# PCU_Testboard.net
KiCad netlist of a schematic drawn in EAGLE
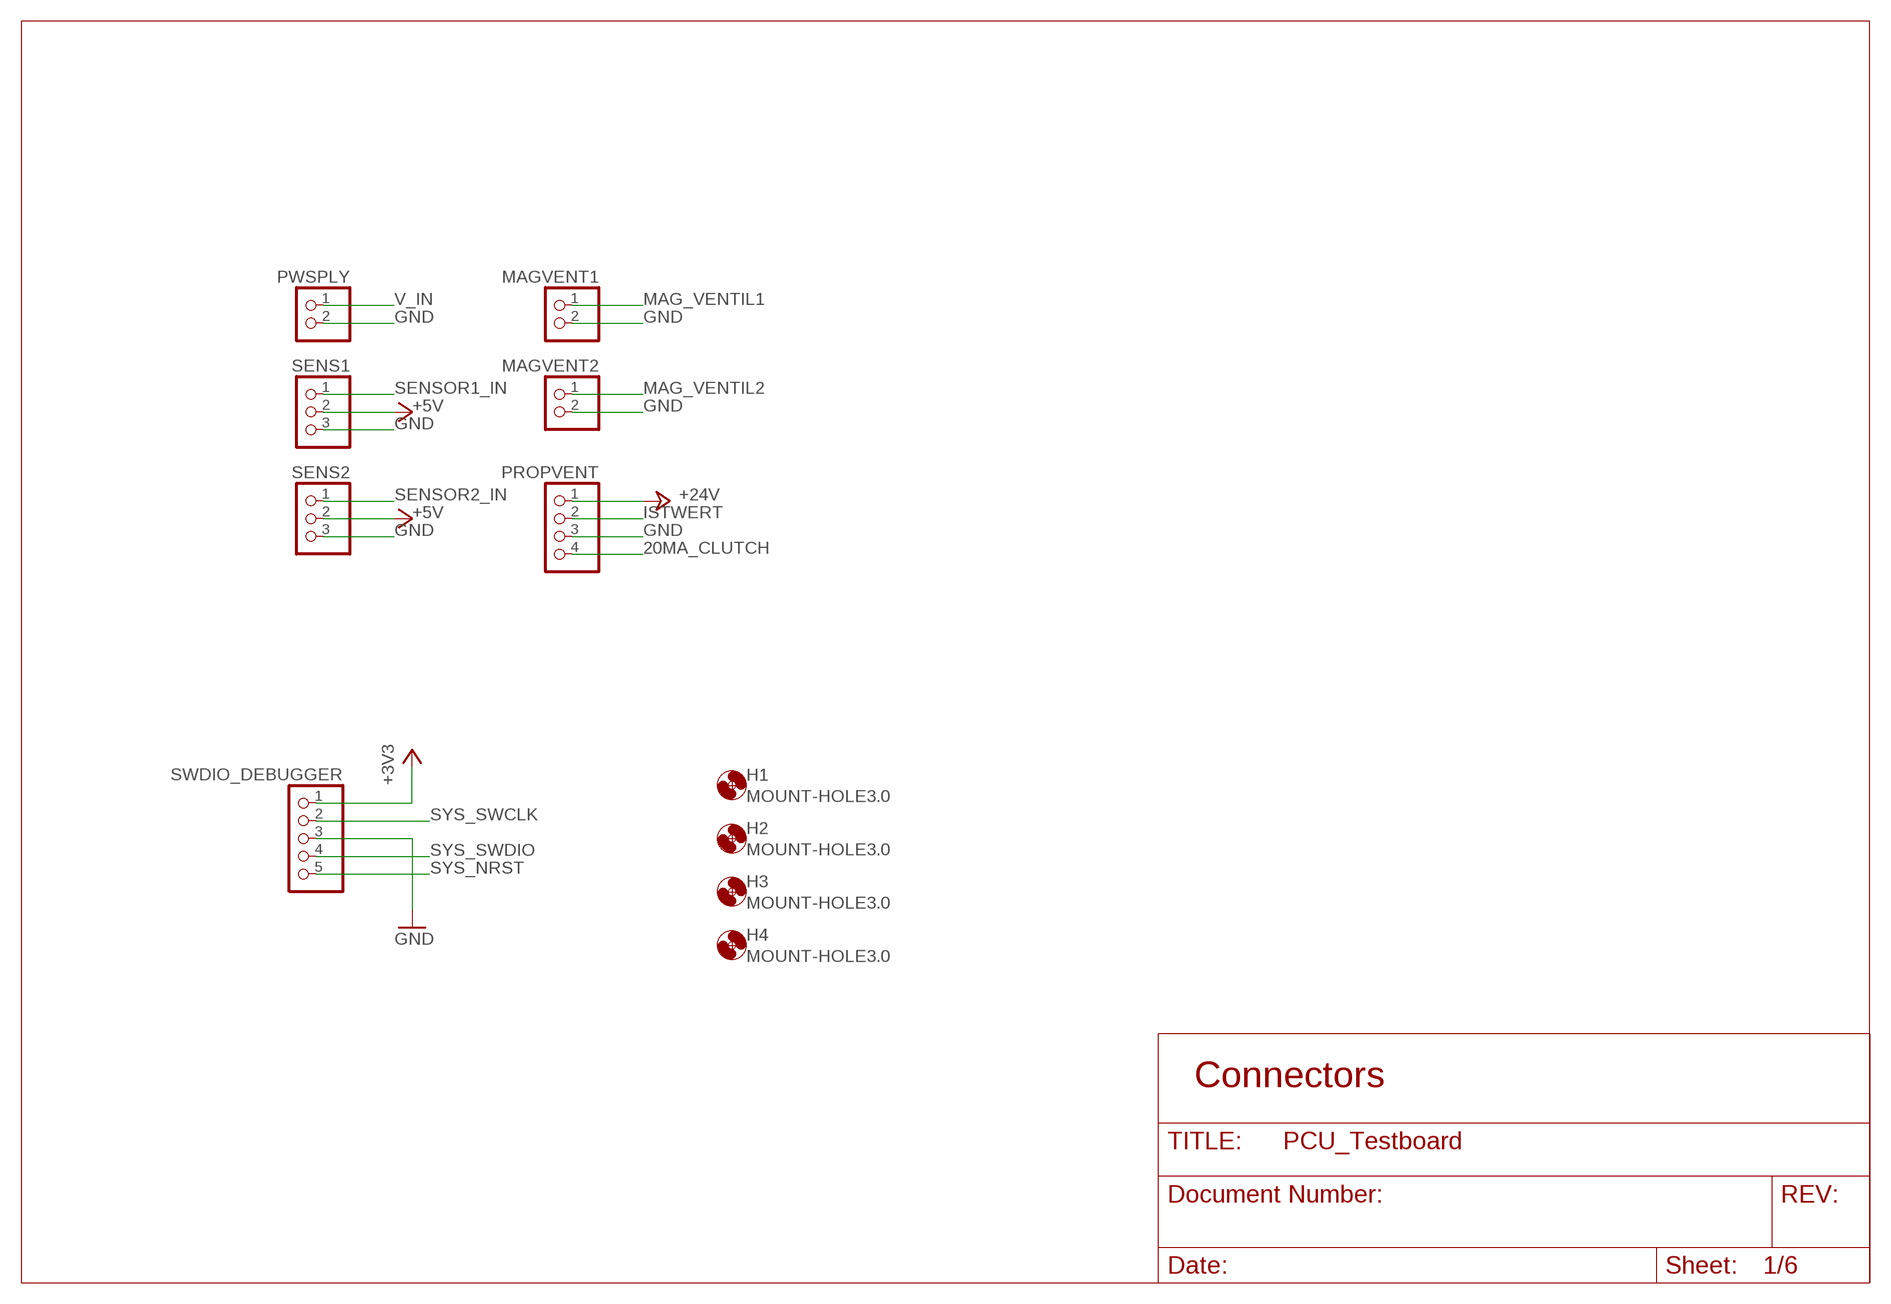
[diagram p0: schematic, sheet 1]
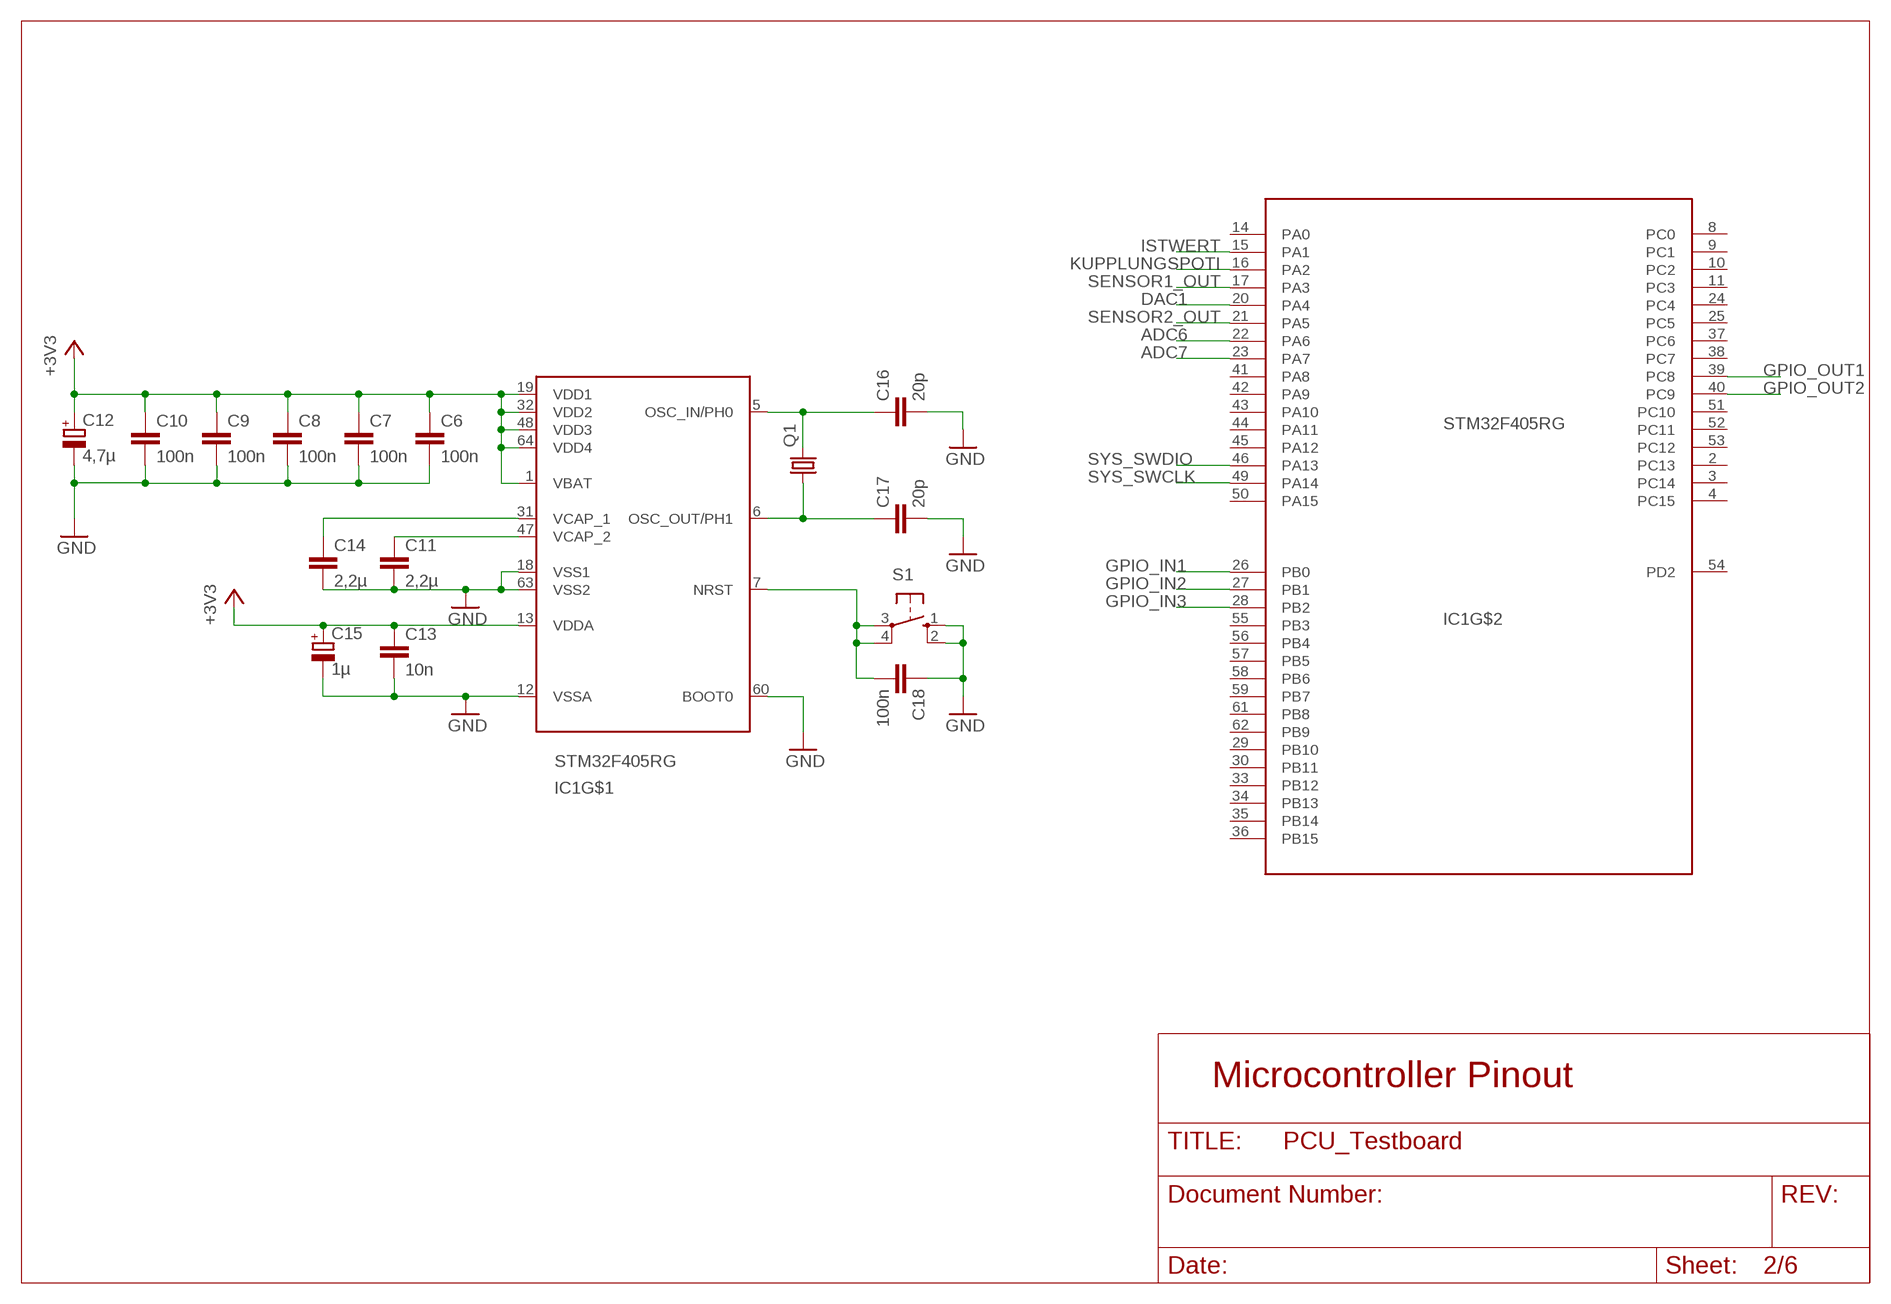
[diagram p1: schematic, sheet 2]
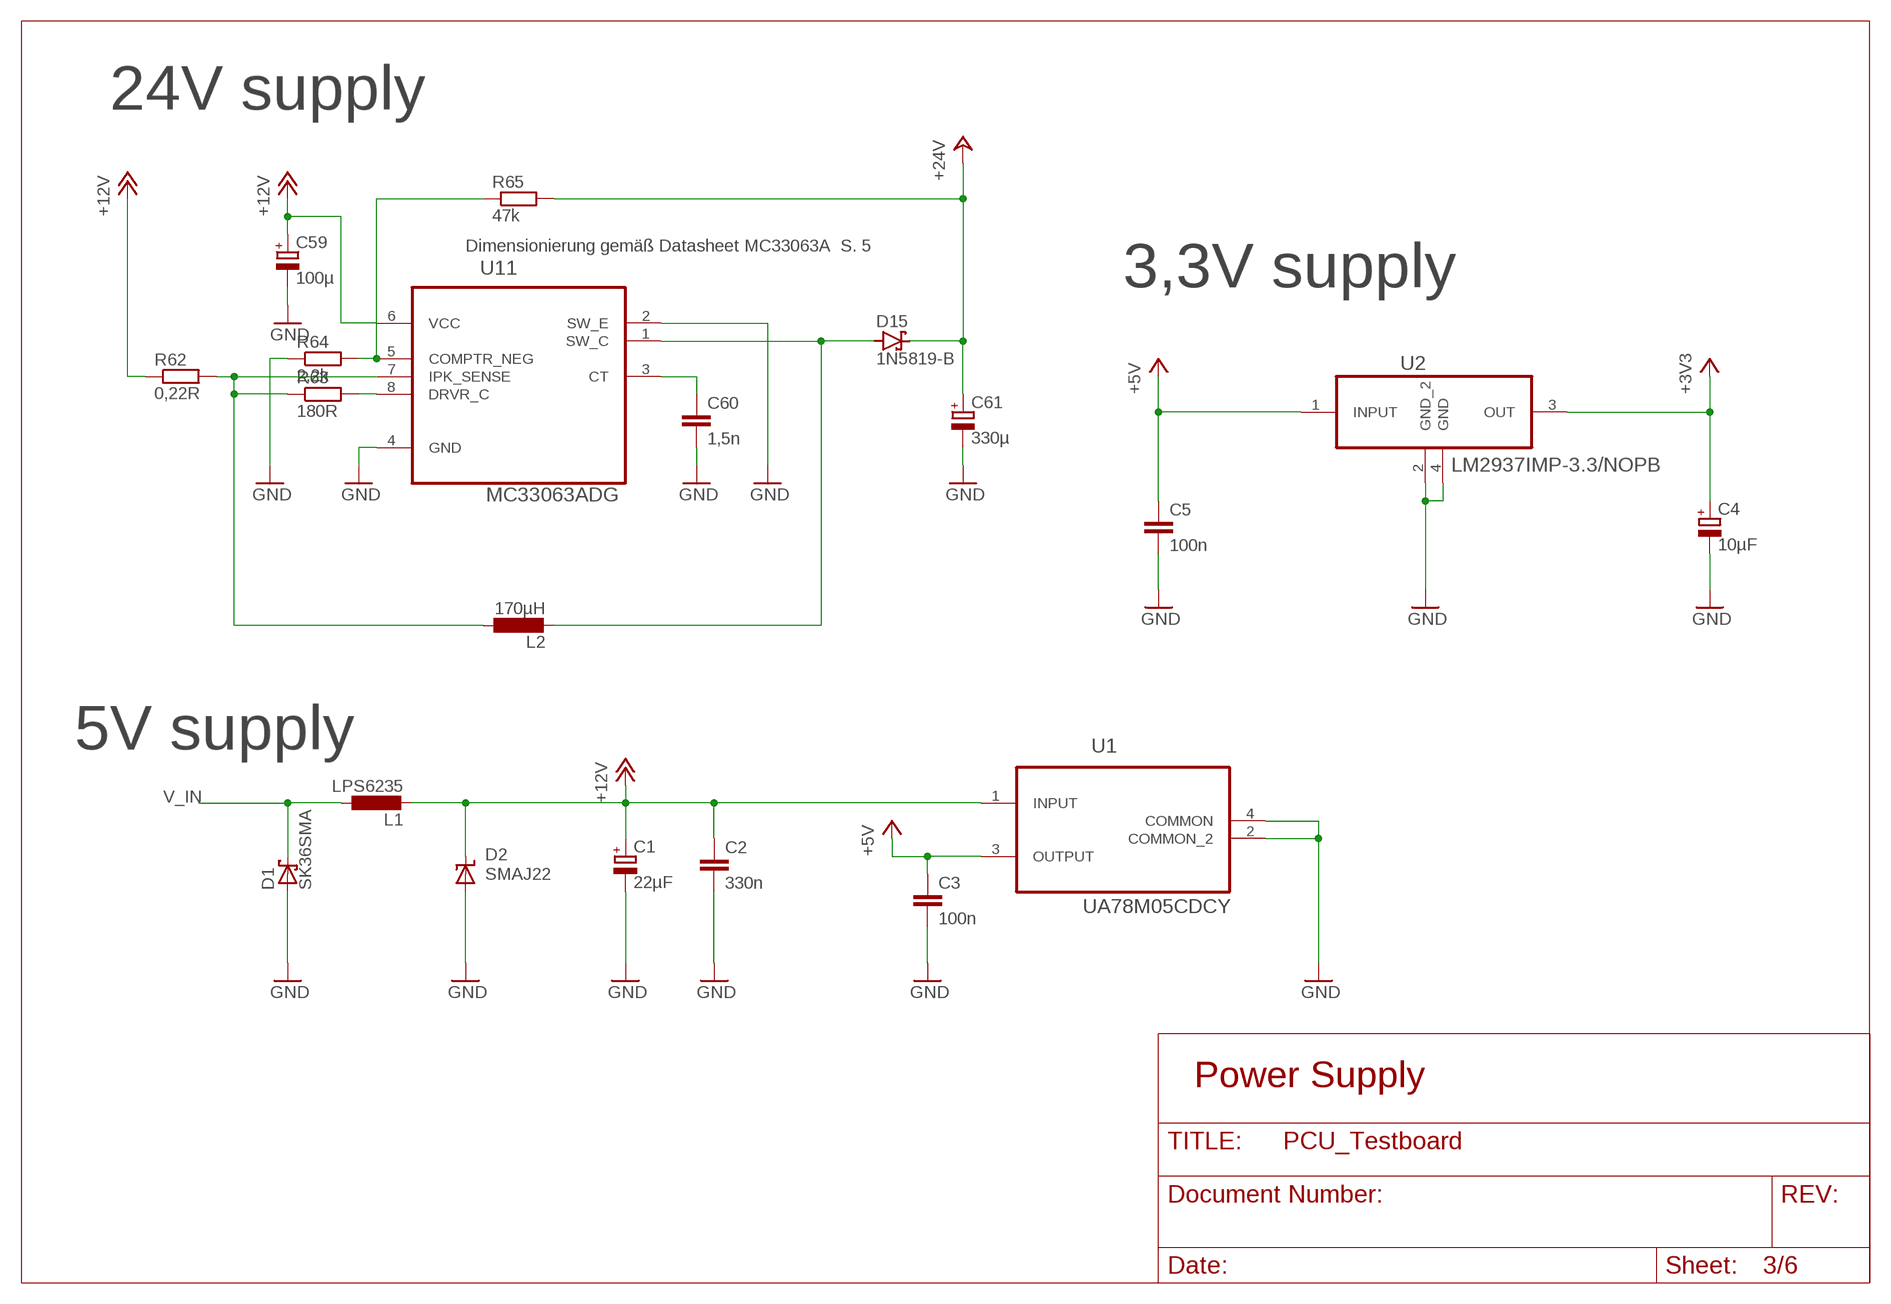
[diagram p2: schematic, sheet 3]
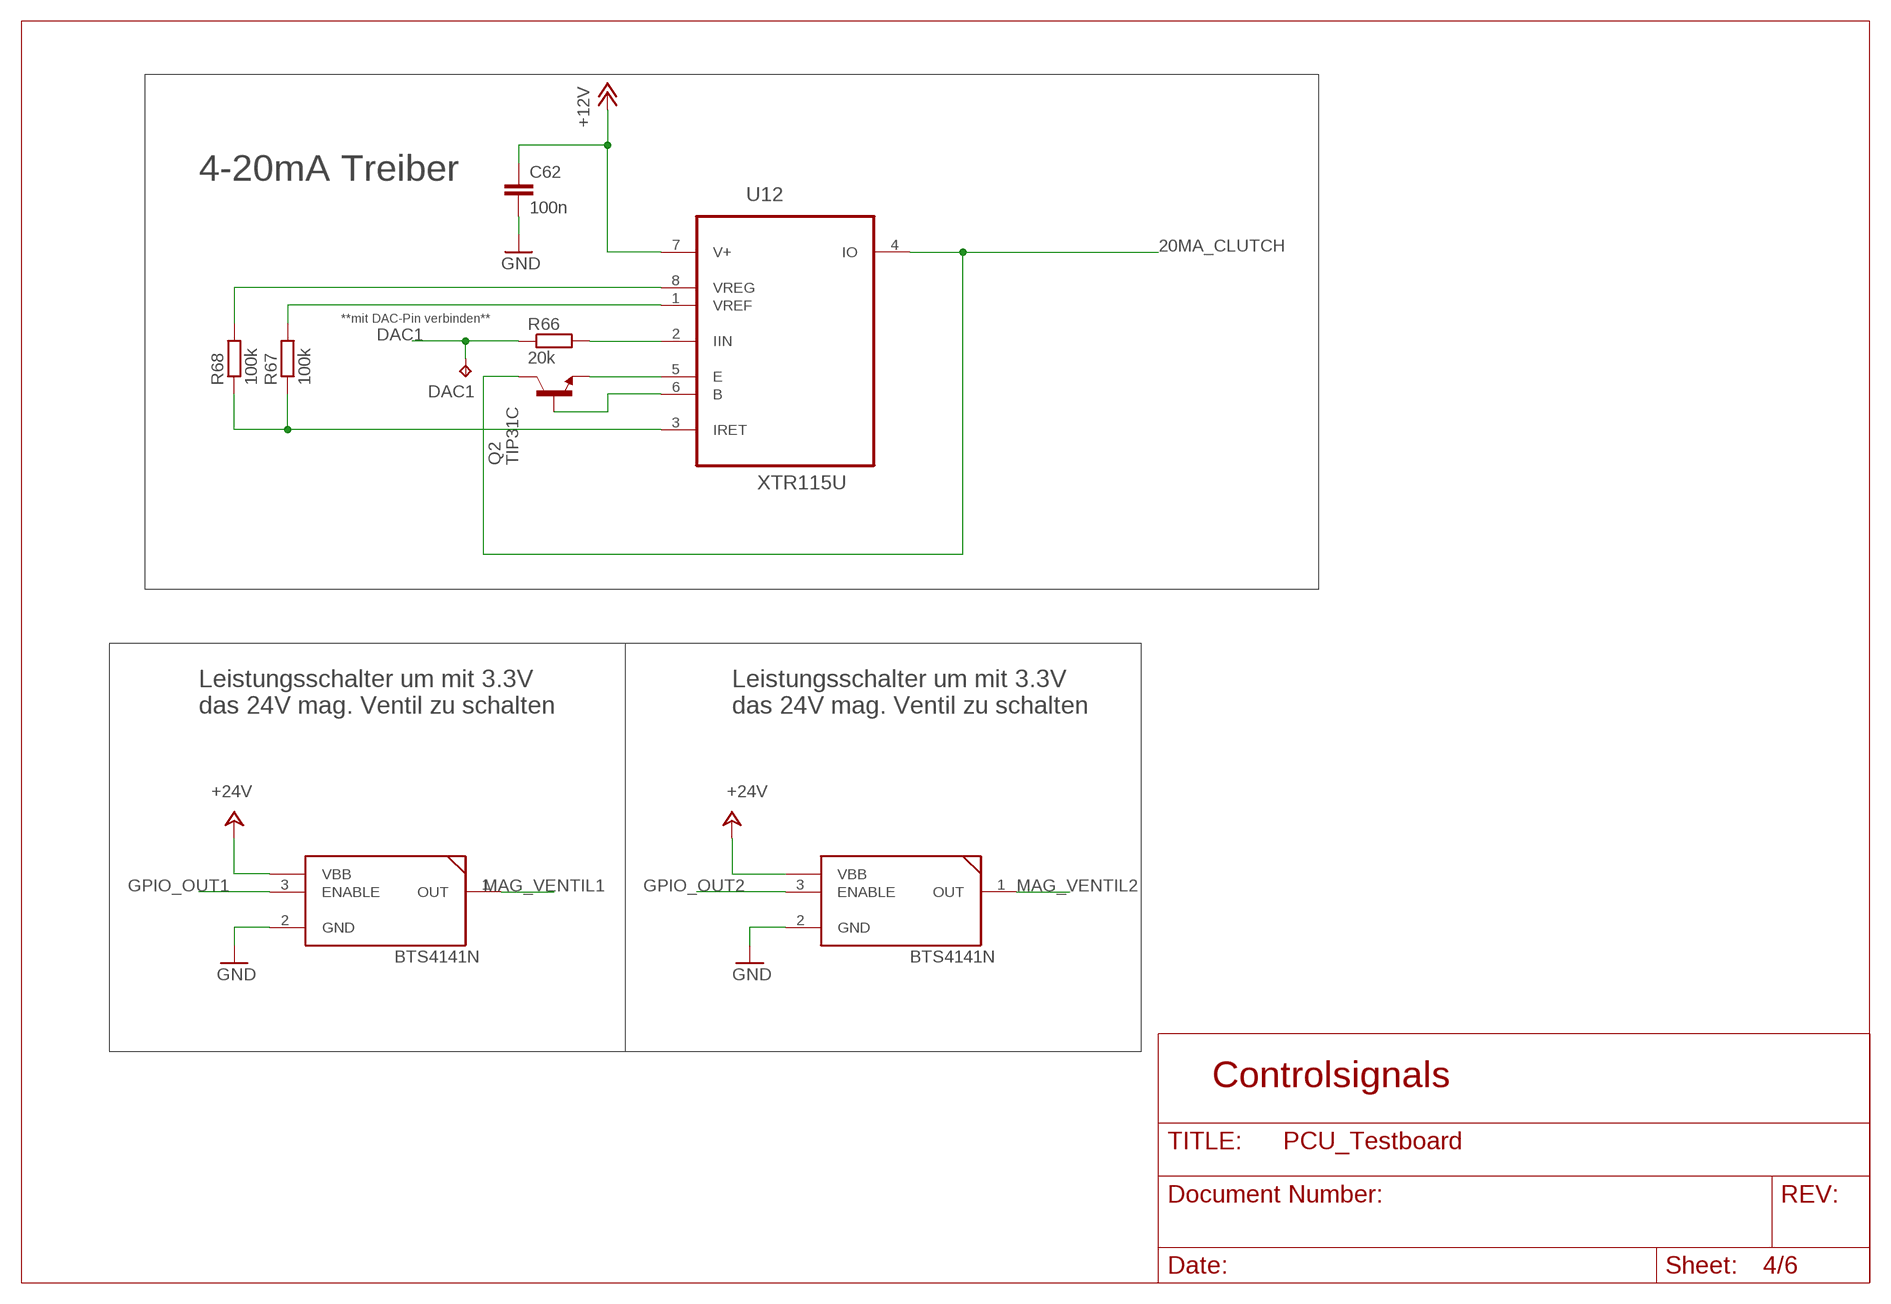
[diagram p3: schematic, sheet 4]
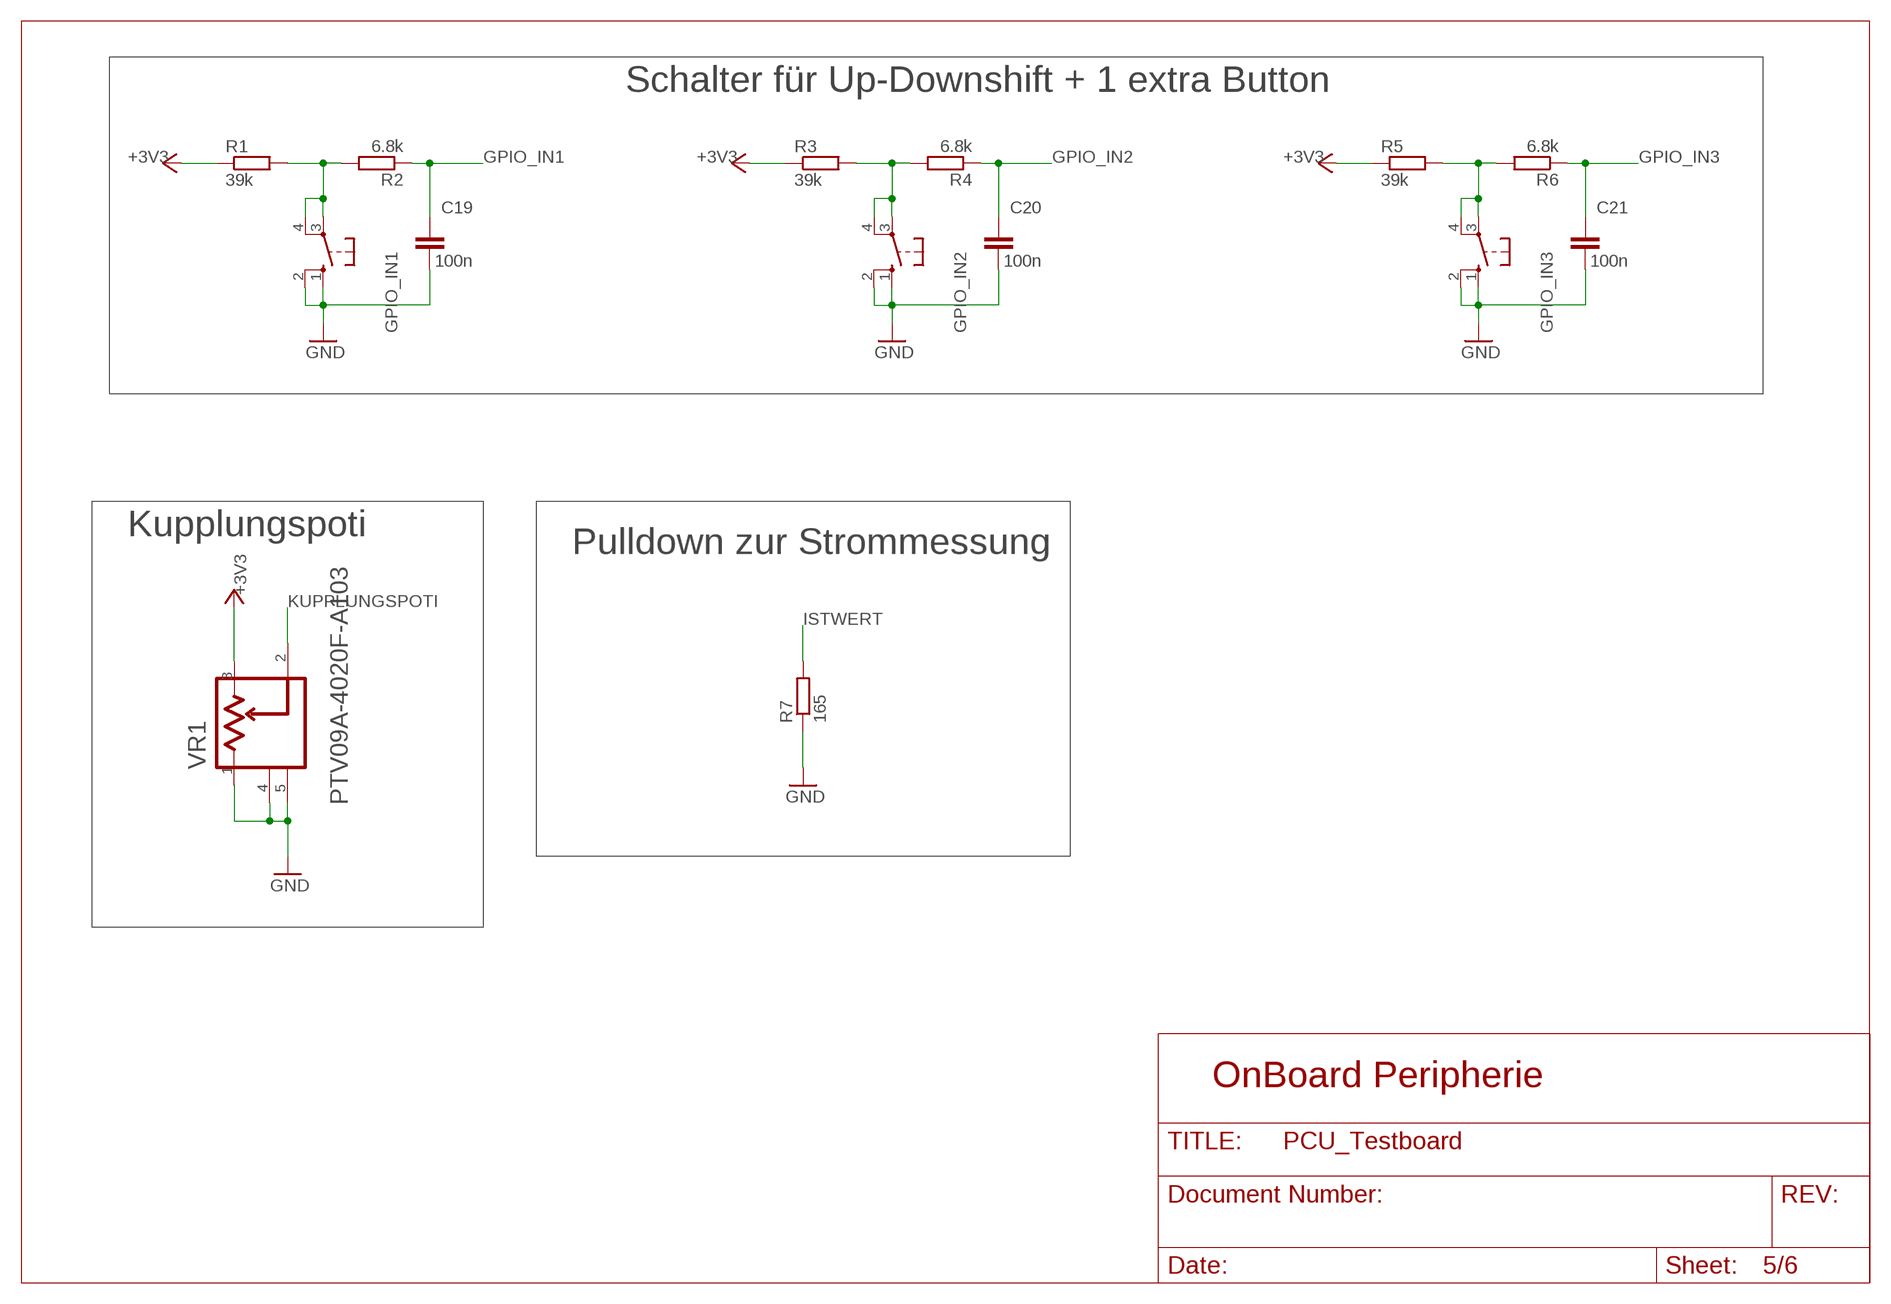
[diagram p4: schematic, sheet 5]
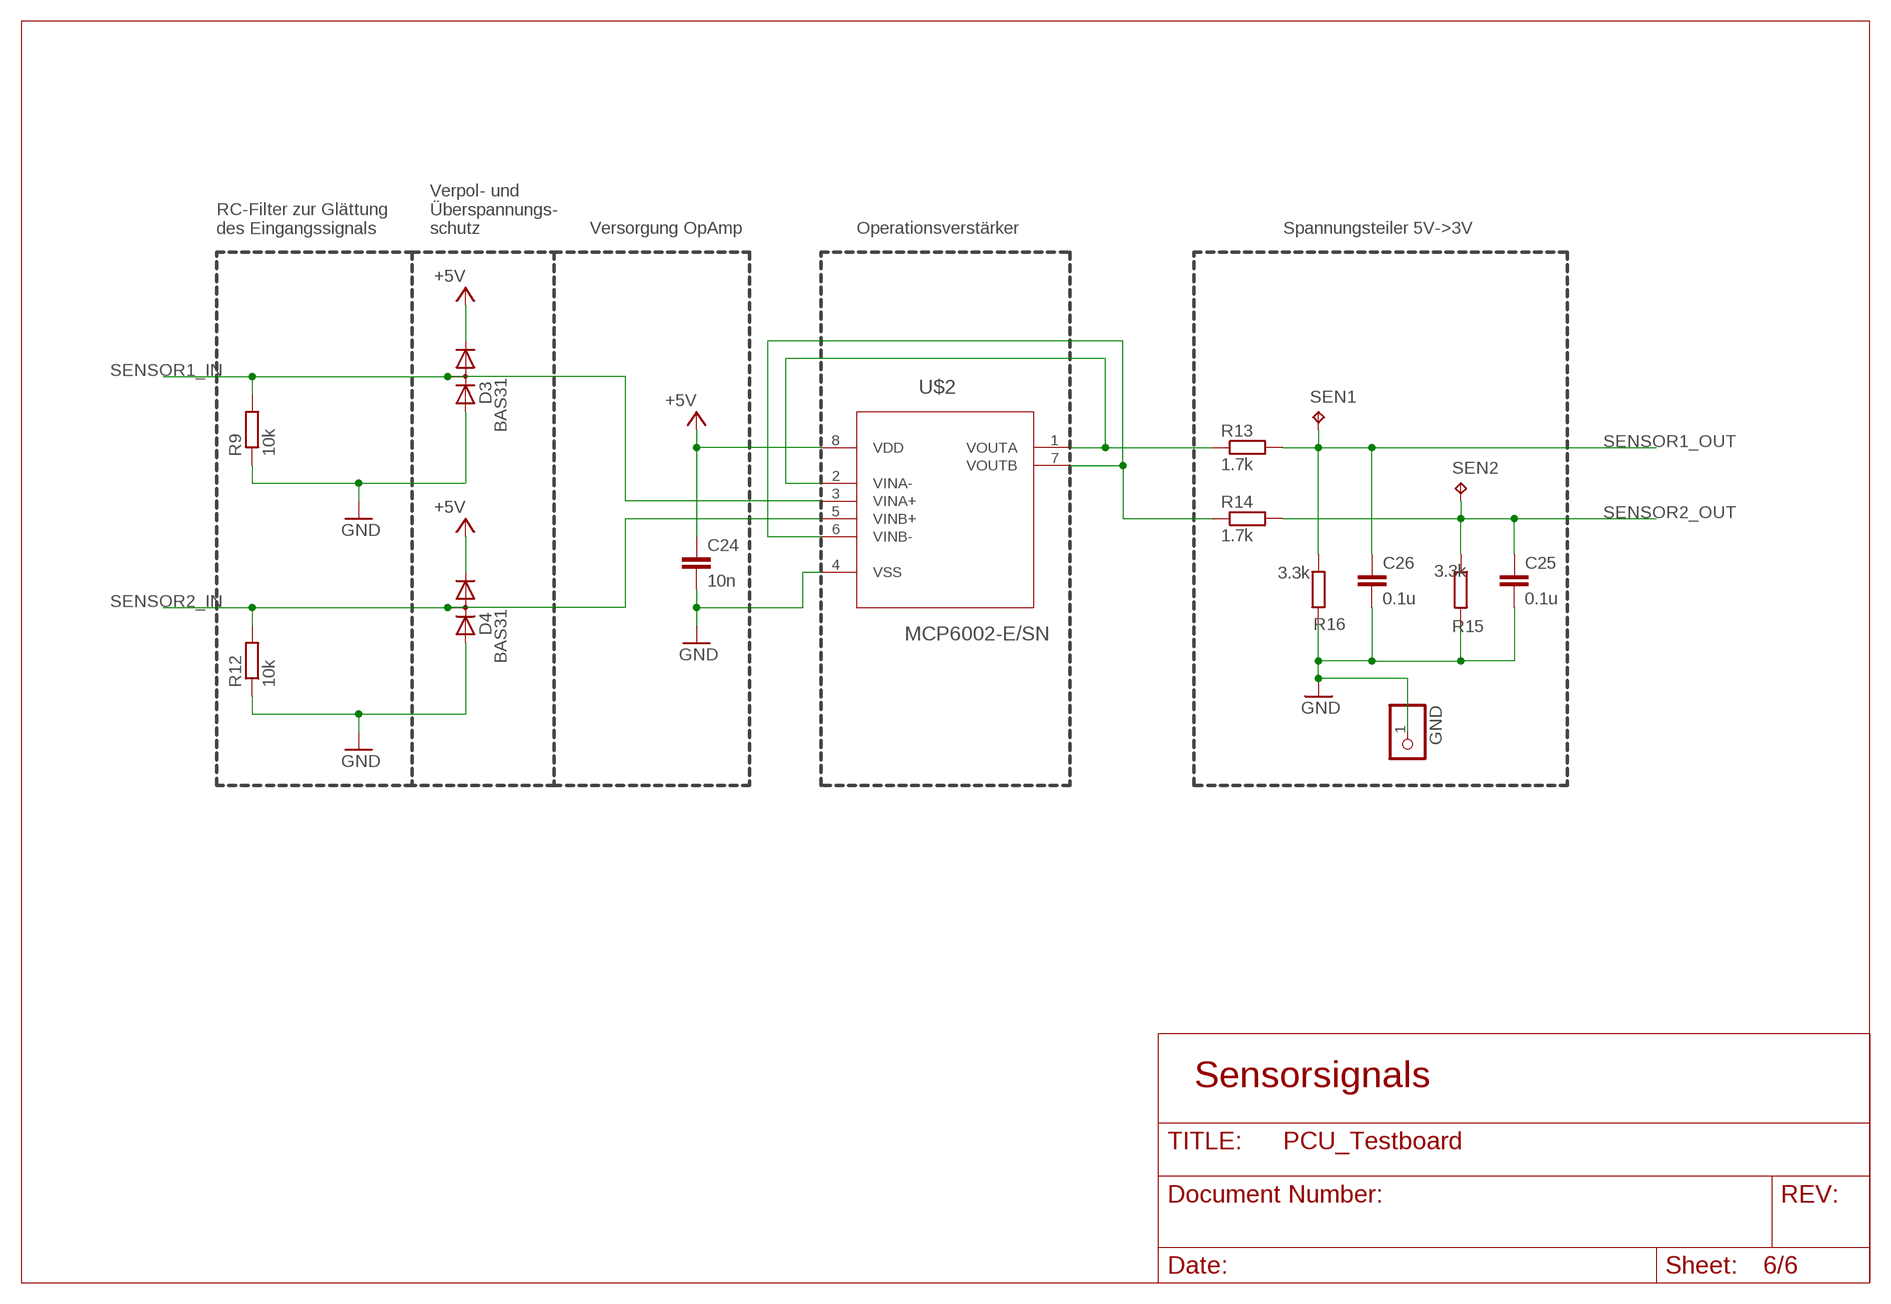
[diagram p5: schematic, sheet 6]

(export (version "E")
  (design (tool "Eeschema 10.0.6"))
  (components
    (comp (ref "C6")
      (value "100n")
      (footprint "eagle-import:C0603")
      (libsource (lib "eagle-import") (part "C-EUC0603"))
    )
    (comp (ref "C7")
      (value "100n")
      (footprint "eagle-import:C0603")
      (libsource (lib "eagle-import") (part "C-EUC0603"))
    )
    (comp (ref "C8")
      (value "100n")
      (footprint "eagle-import:C0603")
      (libsource (lib "eagle-import") (part "C-EUC0603"))
    )
    (comp (ref "C9")
      (value "100n")
      (footprint "eagle-import:C0603")
      (libsource (lib "eagle-import") (part "C-EUC0603"))
    )
    (comp (ref "C10")
      (value "100n")
      (footprint "eagle-import:C0603")
      (libsource (lib "eagle-import") (part "C-EUC0603"))
    )
    (comp (ref "C11")
      (value "2,2µ")
      (footprint "eagle-import:C0603")
      (libsource (lib "eagle-import") (part "C-EUC0603"))
    )
    (comp (ref "C12")
      (value "4,7µ")
      (footprint "eagle-import:153CLV-0505")
      (libsource (lib "eagle-import") (part "CPOL-EU153CLV-0505"))
    )
    (comp (ref "C13")
      (value "10n")
      (footprint "eagle-import:C0603")
      (libsource (lib "eagle-import") (part "C-EUC0603"))
    )
    (comp (ref "C14")
      (value "2,2µ")
      (footprint "eagle-import:C0603")
      (libsource (lib "eagle-import") (part "C-EUC0603"))
    )
    (comp (ref "C15")
      (value "1µ")
      (footprint "eagle-import:153CLV-0505")
      (libsource (lib "eagle-import") (part "CPOL-EU153CLV-0505"))
    )
    (comp (ref "C16")
      (value "20p")
      (footprint "eagle-import:C0603")
      (libsource (lib "eagle-import") (part "C-EUC0603"))
    )
    (comp (ref "C17")
      (value "20p")
      (footprint "eagle-import:C0603")
      (libsource (lib "eagle-import") (part "C-EUC0603"))
    )
    (comp (ref "C18")
      (value "100n")
      (footprint "eagle-import:C0603")
      (libsource (lib "eagle-import") (part "C-EUC0603"))
    )
    (comp (ref "IC1")
      (value "STM32F405RG")
      (footprint "eagle-import:LQFP64")
      (libsource (lib "eagle-import") (part "STM32F405RG"))
    )
    (comp (ref "Q1")
      (value "CRYSTALHC49UP")
      (footprint "eagle-import:HC49UP")
      (libsource (lib "eagle-import") (part "CRYSTALHC49UP"))
    )
    (comp (ref "S1")
      (value "10-XX")
      (footprint "eagle-import:B3F-10XX")
      (fields (field (name "MPN") "B3F-1000"))
      (libsource (lib "eagle-import") (part "10-XX"))
    )
    (comp (ref "H1")
      (value "MOUNT-HOLE3.0")
      (footprint "eagle-import:3,0")
      (libsource (lib "eagle-import") (part "MOUNT-HOLE3.0"))
    )
    (comp (ref "H2")
      (value "MOUNT-HOLE3.0")
      (footprint "eagle-import:3,0")
      (libsource (lib "eagle-import") (part "MOUNT-HOLE3.0"))
    )
    (comp (ref "H3")
      (value "MOUNT-HOLE3.0")
      (footprint "eagle-import:3,0")
      (libsource (lib "eagle-import") (part "MOUNT-HOLE3.0"))
    )
    (comp (ref "H4")
      (value "MOUNT-HOLE3.0")
      (footprint "eagle-import:3,0")
      (libsource (lib "eagle-import") (part "MOUNT-HOLE3.0"))
    )
    (comp (ref "MAGVENT1")
      (value "PINHD-1X2")
      (footprint "eagle-import:1X02")
      (libsource (lib "eagle-import") (part "PINHD-1X2"))
    )
    (comp (ref "MAGVENT2")
      (value "PINHD-1X2")
      (footprint "eagle-import:1X02")
      (libsource (lib "eagle-import") (part "PINHD-1X2"))
    )
    (comp (ref "PROPVENT")
      (value "PINHD-1X4")
      (footprint "eagle-import:1X04")
      (libsource (lib "eagle-import") (part "PINHD-1X4"))
    )
    (comp (ref "PWSPLY")
      (value "PINHD-1X2")
      (footprint "eagle-import:1X02")
      (libsource (lib "eagle-import") (part "PINHD-1X2"))
    )
    (comp (ref "SENS1")
      (value "PINHD-1X3")
      (footprint "eagle-import:1X03")
      (libsource (lib "eagle-import") (part "PINHD-1X3"))
    )
    (comp (ref "SENS2")
      (value "PINHD-1X3")
      (footprint "eagle-import:1X03")
      (libsource (lib "eagle-import") (part "PINHD-1X3"))
    )
    (comp (ref "SWDIO_DEBUGGER")
      (value "PINHD-1X5")
      (footprint "eagle-import:1X05")
      (libsource (lib "eagle-import") (part "PINHD-1X5"))
    )
    (comp (ref "C24")
      (value "10n")
      (footprint "eagle-import:C0603")
      (libsource (lib "eagle-import") (part "C-EUC0603"))
    )
    (comp (ref "C25")
      (value "0.1u")
      (footprint "eagle-import:C0603")
      (libsource (lib "eagle-import") (part "C-EUC0603"))
    )
    (comp (ref "C26")
      (value "0.1u")
      (footprint "eagle-import:C0603")
      (libsource (lib "eagle-import") (part "C-EUC0603"))
    )
    (comp (ref "D3")
      (value "BAS31")
      (footprint "eagle-import:SOT23")
      (libsource (lib "eagle-import") (part "BAS31"))
    )
    (comp (ref "D4")
      (value "BAS31")
      (footprint "eagle-import:SOT23")
      (libsource (lib "eagle-import") (part "BAS31"))
    )
    (comp (ref "GND")
      (value "PINHD-1X1")
      (footprint "eagle-import:1X01")
      (libsource (lib "eagle-import") (part "PINHD-1X1"))
    )
    (comp (ref "R9")
      (value "10k")
      (footprint "eagle-import:R0805")
      (libsource (lib "eagle-import") (part "R-EU_R0805"))
    )
    (comp (ref "R12")
      (value "10k")
      (footprint "eagle-import:R0805")
      (libsource (lib "eagle-import") (part "R-EU_R0805"))
    )
    (comp (ref "R13")
      (value "1.7k")
      (footprint "eagle-import:R0805")
      (libsource (lib "eagle-import") (part "R-EU_R0805"))
    )
    (comp (ref "R14")
      (value "1.7k")
      (footprint "eagle-import:R0805")
      (libsource (lib "eagle-import") (part "R-EU_R0805"))
    )
    (comp (ref "R15")
      (value "3.3k")
      (footprint "eagle-import:R0805")
      (libsource (lib "eagle-import") (part "R-EU_R0805"))
    )
    (comp (ref "R16")
      (value "3.3k")
      (footprint "eagle-import:R0805")
      (libsource (lib "eagle-import") (part "R-EU_R0805"))
    )
    (comp (ref "SEN1")
      (value "TPB1,27")
      (footprint "eagle-import:B1,27")
      (libsource (lib "eagle-import") (part "TPB1,27"))
    )
    (comp (ref "SEN2")
      (value "TPB1,27")
      (footprint "eagle-import:B1,27")
      (libsource (lib "eagle-import") (part "TPB1,27"))
    )
    (comp (ref "U$2")
      (value "MCP6002-E/SN")
      (footprint "eagle-import:SOIC127P600X175-8N")
      (libsource (lib "eagle-import") (part "MCP6002-E/SN"))
    )
    (comp (ref "C62")
      (value "100n")
      (footprint "eagle-import:C0603")
      (libsource (lib "eagle-import") (part "C-EUC0603"))
    )
    (comp (ref "DAC1")
      (value "TPB1,27")
      (footprint "eagle-import:B1,27")
      (libsource (lib "eagle-import") (part "TPB1,27"))
    )
    (comp (ref "Q2")
      (value "TIP31C")
      (footprint "eagle-import:TO220")
      (libsource (lib "eagle-import") (part "TIP31C"))
    )
    (comp (ref "R66")
      (value "20k")
      (footprint "eagle-import:R0603")
      (libsource (lib "eagle-import") (part "R-EU_R0603"))
    )
    (comp (ref "R67")
      (value "100k")
      (footprint "eagle-import:R0603")
      (libsource (lib "eagle-import") (part "R-EU_R0603"))
    )
    (comp (ref "R68")
      (value "100k")
      (footprint "eagle-import:R0603")
      (libsource (lib "eagle-import") (part "R-EU_R0603"))
    )
    (comp (ref "U$1")
      (value "BTS4141N")
      (footprint "eagle-import:SOT223")
      (libsource (lib "eagle-import") (part "BTS4141N"))
    )
    (comp (ref "U$4")
      (value "BTS4141N")
      (footprint "eagle-import:SOT223")
      (libsource (lib "eagle-import") (part "BTS4141N"))
    )
    (comp (ref "U12")
      (value "XTR115U")
      (footprint "eagle-import:SOIC127P600X175-8N")
      (libsource (lib "eagle-import") (part "XTR115U"))
    )
    (comp (ref "C1")
      (value "22µF")
      (footprint "eagle-import:153CLV-0605")
      (libsource (lib "eagle-import") (part "CPOL-EU153CLV-0605"))
    )
    (comp (ref "C2")
      (value "330n")
      (footprint "eagle-import:C0603")
      (libsource (lib "eagle-import") (part "C-EUC0603"))
    )
    (comp (ref "C3")
      (value "100n")
      (footprint "eagle-import:C0603")
      (libsource (lib "eagle-import") (part "C-EUC0603"))
    )
    (comp (ref "C4")
      (value "10µF")
      (footprint "eagle-import:153CLV-0807")
      (libsource (lib "eagle-import") (part "CPOL-EU153CLV-0807"))
    )
    (comp (ref "C5")
      (value "100n")
      (footprint "eagle-import:C0603")
      (libsource (lib "eagle-import") (part "C-EUC0603"))
    )
    (comp (ref "C59")
      (value "100µ")
      (footprint "eagle-import:150CLZ-0810")
      (libsource (lib "eagle-import") (part "CPOL-EU150CLZ-0810"))
    )
    (comp (ref "C60")
      (value "1,5n")
      (footprint "eagle-import:C0603")
      (libsource (lib "eagle-import") (part "C-EUC0603"))
    )
    (comp (ref "C61")
      (value "330µ")
      (footprint "eagle-import:153CLV-1010")
      (libsource (lib "eagle-import") (part "CPOL-EU153CLV-1010"))
    )
    (comp (ref "D1")
      (value "SK36SMA")
      (footprint "eagle-import:DO214AC")
      (libsource (lib "eagle-import") (part "SK36SMA"))
    )
    (comp (ref "D2")
      (value "SMAJ22")
      (footprint "eagle-import:SMA-DO214AC")
      (libsource (lib "eagle-import") (part "SMAJ22"))
    )
    (comp (ref "D15")
      (value "1N5819-B")
      (footprint "eagle-import:DO41-7.6")
      (libsource (lib "eagle-import") (part "1N5819-B"))
    )
    (comp (ref "L1")
      (value "LPS6235")
      (footprint "eagle-import:LPS6235")
      (libsource (lib "eagle-import") (part "LPS6235"))
    )
    (comp (ref "L2")
      (value "170µH")
      (footprint "eagle-import:LPS6235")
      (libsource (lib "eagle-import") (part "LPS6235"))
    )
    (comp (ref "R62")
      (value "0,22R")
      (footprint "eagle-import:R0603")
      (libsource (lib "eagle-import") (part "R-EU_R0603"))
    )
    (comp (ref "R63")
      (value "180R")
      (footprint "eagle-import:R0603")
      (libsource (lib "eagle-import") (part "R-EU_R0603"))
    )
    (comp (ref "R64")
      (value "2,2k")
      (footprint "eagle-import:R0603")
      (libsource (lib "eagle-import") (part "R-EU_R0603"))
    )
    (comp (ref "R65")
      (value "47k")
      (footprint "eagle-import:R0603")
      (libsource (lib "eagle-import") (part "R-EU_R0603"))
    )
    (comp (ref "U1")
      (value "UA78M05CDCY")
      (footprint "eagle-import:SOT230P700X180-4N")
      (libsource (lib "eagle-import") (part "UA78M05CDCY"))
    )
    (comp (ref "U2")
      (value "LM2937IMP-3.3/NOPB")
      (footprint "eagle-import:SOT230P700X180-4N")
      (libsource (lib "eagle-import") (part "LM2937IMP-3.3/NOPB"))
    )
    (comp (ref "U11")
      (value "MC33063ADG")
      (footprint "eagle-import:SOIC127P600X175-8N")
      (libsource (lib "eagle-import") (part "MC33063ADG"))
    )
    (comp (ref "C19")
      (value "100n")
      (footprint "eagle-import:C0603")
      (libsource (lib "eagle-import") (part "C-EUC0603"))
    )
    (comp (ref "C20")
      (value "100n")
      (footprint "eagle-import:C0603")
      (libsource (lib "eagle-import") (part "C-EUC0603"))
    )
    (comp (ref "C21")
      (value "100n")
      (footprint "eagle-import:C0603")
      (libsource (lib "eagle-import") (part "C-EUC0603"))
    )
    (comp (ref "GPIO_IN1")
      (value "10-XX")
      (footprint "eagle-import:B3F-10XX")
      (fields (field (name "MPN") "B3F-1000"))
      (libsource (lib "eagle-import") (part "10-XX"))
    )
    (comp (ref "GPIO_IN2")
      (value "10-XX")
      (footprint "eagle-import:B3F-10XX")
      (fields (field (name "MPN") "B3F-1000"))
      (libsource (lib "eagle-import") (part "10-XX"))
    )
    (comp (ref "GPIO_IN3")
      (value "10-XX")
      (footprint "eagle-import:B3F-10XX")
      (fields (field (name "MPN") "B3F-1000"))
      (libsource (lib "eagle-import") (part "10-XX"))
    )
    (comp (ref "R1")
      (value "39k")
      (footprint "eagle-import:R0805")
      (libsource (lib "eagle-import") (part "R-EU_R0805"))
    )
    (comp (ref "R2")
      (value "6.8k")
      (footprint "eagle-import:R0805")
      (libsource (lib "eagle-import") (part "R-EU_R0805"))
    )
    (comp (ref "R3")
      (value "39k")
      (footprint "eagle-import:R0805")
      (libsource (lib "eagle-import") (part "R-EU_R0805"))
    )
    (comp (ref "R4")
      (value "6.8k")
      (footprint "eagle-import:R0805")
      (libsource (lib "eagle-import") (part "R-EU_R0805"))
    )
    (comp (ref "R5")
      (value "39k")
      (footprint "eagle-import:R0805")
      (libsource (lib "eagle-import") (part "R-EU_R0805"))
    )
    (comp (ref "R6")
      (value "6.8k")
      (footprint "eagle-import:R0805")
      (libsource (lib "eagle-import") (part "R-EU_R0805"))
    )
    (comp (ref "R7")
      (value "165")
      (footprint "eagle-import:R0805")
      (libsource (lib "eagle-import") (part "R-EU_R0805"))
    )
    (comp (ref "VR1")
      (value "BOURNS_PTV09A-4020F-A103BOURNS_PTV09A-4020F-A103_0_0")
      (footprint "eagle-import:BOURNS_PTV09A-4020F-A103_0")
      (fields
        (field (name "DIGIKEY_PART_NUMBER") "PTV09A-4020F-A103-ND")
        (field (name "MF") "Bourns")
        (field (name "MOUSER_PART_NUMBER") "652-PTV09A-4020FA103")
      )
      (libsource (lib "eagle-import") (part "BOURNS_PTV09A-4020F-A103BOURNS_PTV09A-4020F-A103_0_0"))
    )
  )
  (nets
    (net (code "1") (name "+3V3") (class "Default")
      (node (ref "C10") (pin "1") (pinfunction "1_1") (pintype "passive"))
      (node (ref "C12") (pin "+") (pinfunction "+_+") (pintype "passive"))
      (node (ref "C13") (pin "1") (pinfunction "1_1") (pintype "passive"))
      (node (ref "C15") (pin "+") (pinfunction "+_+") (pintype "passive"))
      (node (ref "C4") (pin "+") (pinfunction "+_+") (pintype "passive"))
      (node (ref "C6") (pin "1") (pinfunction "1_1") (pintype "passive"))
      (node (ref "C7") (pin "1") (pinfunction "1_1") (pintype "passive"))
      (node (ref "C8") (pin "1") (pinfunction "1_1") (pintype "passive"))
      (node (ref "C9") (pin "1") (pinfunction "1_1") (pintype "passive"))
      (node (ref "IC1") (pin "1") (pinfunction "VBAT_1") (pintype "bidirectional"))
      (node (ref "IC1") (pin "13") (pinfunction "VDDA_13") (pintype "bidirectional"))
      (node (ref "IC1") (pin "19") (pinfunction "VDD1_19") (pintype "bidirectional"))
      (node (ref "IC1") (pin "32") (pinfunction "VDD2_32") (pintype "bidirectional"))
      (node (ref "IC1") (pin "48") (pinfunction "VDD3_48") (pintype "bidirectional"))
      (node (ref "IC1") (pin "64") (pinfunction "VDD4_64") (pintype "bidirectional"))
      (node (ref "R1") (pin "1") (pinfunction "1_1") (pintype "passive"))
      (node (ref "R3") (pin "1") (pinfunction "1_1") (pintype "passive"))
      (node (ref "R5") (pin "1") (pinfunction "1_1") (pintype "passive"))
      (node (ref "SWDIO_DEBUGGER") (pin "1") (pinfunction "1_1") (pintype "passive"))
      (node (ref "U2") (pin "3") (pinfunction "OUT_3") (pintype "output"))
      (node (ref "VR1") (pin "3") (pinfunction "3_3") (pintype "bidirectional"))
    )
    (net (code "2") (name "+5V") (class "Default")
      (node (ref "C24") (pin "1") (pinfunction "1_1") (pintype "passive"))
      (node (ref "C3") (pin "1") (pinfunction "1_1") (pintype "passive"))
      (node (ref "C5") (pin "1") (pinfunction "1_1") (pintype "passive"))
      (node (ref "D3") (pin "2") (pinfunction "C_2") (pintype "passive"))
      (node (ref "D4") (pin "2") (pinfunction "C_2") (pintype "passive"))
      (node (ref "SENS1") (pin "2") (pinfunction "2_2") (pintype "passive"))
      (node (ref "SENS2") (pin "2") (pinfunction "2_2") (pintype "passive"))
      (node (ref "U$2") (pin "8") (pinfunction "VDD_8") (pintype "power_in"))
      (node (ref "U1") (pin "3") (pinfunction "OUTPUT_3") (pintype "input"))
      (node (ref "U2") (pin "1") (pinfunction "INPUT_1") (pintype "input"))
    )
    (net (code "3") (name "+12V") (class "Default")
      (node (ref "C1") (pin "+") (pinfunction "+_+") (pintype "passive"))
      (node (ref "C2") (pin "1") (pinfunction "1_1") (pintype "passive"))
      (node (ref "C59") (pin "+") (pinfunction "+_+") (pintype "passive"))
      (node (ref "C62") (pin "1") (pinfunction "1_1") (pintype "passive"))
      (node (ref "D2") (pin "K") (pinfunction "C_K") (pintype "passive"))
      (node (ref "L1") (pin "2") (pinfunction "2_2") (pintype "passive"))
      (node (ref "R62") (pin "1") (pinfunction "1_1") (pintype "passive"))
      (node (ref "U1") (pin "1") (pinfunction "INPUT_1") (pintype "input"))
      (node (ref "U11") (pin "6") (pinfunction "VCC_6") (pintype "power_in"))
      (node (ref "U12") (pin "7") (pinfunction "V+_7") (pintype "power_in"))
    )
    (net (code "4") (name "+24V") (class "Default")
      (node (ref "C61") (pin "+") (pinfunction "+_+") (pintype "passive"))
      (node (ref "D15") (pin "C") (pinfunction "C_C") (pintype "passive"))
      (node (ref "PROPVENT") (pin "1") (pinfunction "1_1") (pintype "passive"))
      (node (ref "R65") (pin "2") (pinfunction "2_2") (pintype "passive"))
      (node (ref "U$1") (pin "4") (pinfunction "VBB_4") (pintype "power_in"))
      (node (ref "U$4") (pin "4") (pinfunction "VBB_4") (pintype "power_in"))
    )
    (net (code "5") (name "20MA_CLUTCH") (class "Default")
      (node (ref "PROPVENT") (pin "4") (pinfunction "4_4") (pintype "passive"))
      (node (ref "Q2") (pin "2") (pinfunction "C_2") (pintype "passive"))
      (node (ref "U12") (pin "4") (pinfunction "IO_4") (pintype "output"))
    )
    (net (code "6") (name "ADC6") (class "Default")
      (node (ref "IC1") (pin "22") (pinfunction "PA6_22") (pintype "bidirectional"))
    )
    (net (code "7") (name "ADC7") (class "Default")
      (node (ref "IC1") (pin "23") (pinfunction "PA7_23") (pintype "bidirectional"))
    )
    (net (code "8") (name "DAC1") (class "Default")
      (node (ref "DAC1") (pin "TP") (pinfunction "TP_TP") (pintype "input"))
      (node (ref "IC1") (pin "20") (pinfunction "PA4_20") (pintype "bidirectional"))
      (node (ref "R66") (pin "1") (pinfunction "1_1") (pintype "passive"))
    )
    (net (code "9") (name "GND") (class "Default")
      (node (ref "C1") (pin "-") (pinfunction "-_-") (pintype "passive"))
      (node (ref "C10") (pin "2") (pinfunction "2_2") (pintype "passive"))
      (node (ref "C11") (pin "2") (pinfunction "2_2") (pintype "passive"))
      (node (ref "C12") (pin "-") (pinfunction "-_-") (pintype "passive"))
      (node (ref "C13") (pin "2") (pinfunction "2_2") (pintype "passive"))
      (node (ref "C14") (pin "2") (pinfunction "2_2") (pintype "passive"))
      (node (ref "C15") (pin "-") (pinfunction "-_-") (pintype "passive"))
      (node (ref "C16") (pin "2") (pinfunction "2_2") (pintype "passive"))
      (node (ref "C17") (pin "2") (pinfunction "2_2") (pintype "passive"))
      (node (ref "C18") (pin "1") (pinfunction "1_1") (pintype "passive"))
      (node (ref "C19") (pin "2") (pinfunction "2_2") (pintype "passive"))
      (node (ref "C2") (pin "2") (pinfunction "2_2") (pintype "passive"))
      (node (ref "C20") (pin "2") (pinfunction "2_2") (pintype "passive"))
      (node (ref "C21") (pin "2") (pinfunction "2_2") (pintype "passive"))
      (node (ref "C24") (pin "2") (pinfunction "2_2") (pintype "passive"))
      (node (ref "C25") (pin "2") (pinfunction "2_2") (pintype "passive"))
      (node (ref "C26") (pin "2") (pinfunction "2_2") (pintype "passive"))
      (node (ref "C3") (pin "2") (pinfunction "2_2") (pintype "passive"))
      (node (ref "C4") (pin "-") (pinfunction "-_-") (pintype "passive"))
      (node (ref "C5") (pin "2") (pinfunction "2_2") (pintype "passive"))
      (node (ref "C59") (pin "-") (pinfunction "-_-") (pintype "passive"))
      (node (ref "C6") (pin "2") (pinfunction "2_2") (pintype "passive"))
      (node (ref "C60") (pin "2") (pinfunction "2_2") (pintype "passive"))
      (node (ref "C61") (pin "-") (pinfunction "-_-") (pintype "passive"))
      (node (ref "C62") (pin "2") (pinfunction "2_2") (pintype "passive"))
      (node (ref "C7") (pin "2") (pinfunction "2_2") (pintype "passive"))
      (node (ref "C8") (pin "2") (pinfunction "2_2") (pintype "passive"))
      (node (ref "C9") (pin "2") (pinfunction "2_2") (pintype "passive"))
      (node (ref "D1") (pin "A") (pinfunction "A_A") (pintype "passive"))
      (node (ref "D2") (pin "A") (pinfunction "A_A") (pintype "passive"))
      (node (ref "D3") (pin "1") (pinfunction "A_1") (pintype "passive"))
      (node (ref "D4") (pin "1") (pinfunction "A_1") (pintype "passive"))
      (node (ref "GND") (pin "1") (pinfunction "1_1") (pintype "passive"))
      (node (ref "GPIO_IN1") (pin "1") (pinfunction "S_1") (pintype "passive"))
      (node (ref "GPIO_IN1") (pin "2") (pinfunction "S1_2") (pintype "passive"))
      (node (ref "GPIO_IN2") (pin "1") (pinfunction "S_1") (pintype "passive"))
      (node (ref "GPIO_IN2") (pin "2") (pinfunction "S1_2") (pintype "passive"))
      (node (ref "GPIO_IN3") (pin "1") (pinfunction "S_1") (pintype "passive"))
      (node (ref "GPIO_IN3") (pin "2") (pinfunction "S1_2") (pintype "passive"))
      (node (ref "IC1") (pin "12") (pinfunction "VSSA_12") (pintype "bidirectional"))
      (node (ref "IC1") (pin "18") (pinfunction "VSS1_18") (pintype "bidirectional"))
      (node (ref "IC1") (pin "60") (pinfunction "BOOT0_60") (pintype "bidirectional"))
      (node (ref "IC1") (pin "63") (pinfunction "VSS2_63") (pintype "bidirectional"))
      (node (ref "MAGVENT1") (pin "2") (pinfunction "2_2") (pintype "passive"))
      (node (ref "MAGVENT2") (pin "2") (pinfunction "2_2") (pintype "passive"))
      (node (ref "PROPVENT") (pin "3") (pinfunction "3_3") (pintype "passive"))
      (node (ref "PWSPLY") (pin "2") (pinfunction "2_2") (pintype "passive"))
      (node (ref "R12") (pin "1") (pinfunction "1_1") (pintype "passive"))
      (node (ref "R15") (pin "2") (pinfunction "2_2") (pintype "passive"))
      (node (ref "R16") (pin "1") (pinfunction "1_1") (pintype "passive"))
      (node (ref "R64") (pin "1") (pinfunction "1_1") (pintype "passive"))
      (node (ref "R7") (pin "1") (pinfunction "1_1") (pintype "passive"))
      (node (ref "R9") (pin "1") (pinfunction "1_1") (pintype "passive"))
      (node (ref "S1") (pin "1") (pinfunction "S_1") (pintype "passive"))
      (node (ref "S1") (pin "2") (pinfunction "S1_2") (pintype "passive"))
      (node (ref "SENS1") (pin "3") (pinfunction "3_3") (pintype "passive"))
      (node (ref "SENS2") (pin "3") (pinfunction "3_3") (pintype "passive"))
      (node (ref "SWDIO_DEBUGGER") (pin "3") (pinfunction "3_3") (pintype "passive"))
      (node (ref "U$1") (pin "2") (pinfunction "GND_2") (pintype "power_in"))
      (node (ref "U$2") (pin "4") (pinfunction "VSS_4") (pintype "power_in"))
      (node (ref "U$4") (pin "2") (pinfunction "GND_2") (pintype "power_in"))
      (node (ref "U1") (pin "2") (pinfunction "COMMON_2_2") (pintype "output"))
      (node (ref "U1") (pin "4") (pinfunction "COMMON_4") (pintype "output"))
      (node (ref "U11") (pin "2") (pinfunction "SW_E_2") (pintype "output"))
      (node (ref "U11") (pin "4") (pinfunction "GND_4") (pintype "passive"))
      (node (ref "U2") (pin "2") (pinfunction "GND_2_2") (pintype "passive"))
      (node (ref "U2") (pin "4") (pinfunction "GND_4") (pintype "passive"))
      (node (ref "VR1") (pin "1") (pinfunction "1_1") (pintype "bidirectional"))
      (node (ref "VR1") (pin "4") (pinfunction "MNT_1_4") (pintype "bidirectional"))
      (node (ref "VR1") (pin "5") (pinfunction "MNT_2_5") (pintype "bidirectional"))
    )
    (net (code "10") (name "GPIO_IN1") (class "Default")
      (node (ref "C19") (pin "1") (pinfunction "1_1") (pintype "passive"))
      (node (ref "IC1") (pin "26") (pinfunction "PB0_26") (pintype "bidirectional"))
      (node (ref "R2") (pin "1") (pinfunction "1_1") (pintype "passive"))
    )
    (net (code "11") (name "GPIO_IN2") (class "Default")
      (node (ref "C20") (pin "1") (pinfunction "1_1") (pintype "passive"))
      (node (ref "IC1") (pin "27") (pinfunction "PB1_27") (pintype "bidirectional"))
      (node (ref "R4") (pin "1") (pinfunction "1_1") (pintype "passive"))
    )
    (net (code "12") (name "GPIO_IN3") (class "Default")
      (node (ref "C21") (pin "1") (pinfunction "1_1") (pintype "passive"))
      (node (ref "IC1") (pin "28") (pinfunction "PB2_28") (pintype "bidirectional"))
      (node (ref "R6") (pin "1") (pinfunction "1_1") (pintype "passive"))
    )
    (net (code "13") (name "GPIO_OUT1") (class "Default")
      (node (ref "IC1") (pin "39") (pinfunction "PC8_39") (pintype "bidirectional"))
      (node (ref "U$1") (pin "3") (pinfunction "ENABLE_3") (pintype "input"))
    )
    (net (code "14") (name "GPIO_OUT2") (class "Default")
      (node (ref "IC1") (pin "40") (pinfunction "PC9_40") (pintype "bidirectional"))
      (node (ref "U$4") (pin "3") (pinfunction "ENABLE_3") (pintype "input"))
    )
    (net (code "15") (name "ISTWERT") (class "Default")
      (node (ref "IC1") (pin "15") (pinfunction "PA1_15") (pintype "bidirectional"))
      (node (ref "PROPVENT") (pin "2") (pinfunction "2_2") (pintype "passive"))
      (node (ref "R7") (pin "2") (pinfunction "2_2") (pintype "passive"))
    )
    (net (code "16") (name "KUPPLUNGSPOTI") (class "Default")
      (node (ref "IC1") (pin "16") (pinfunction "PA2_16") (pintype "bidirectional"))
      (node (ref "VR1") (pin "2") (pinfunction "2_2") (pintype "bidirectional"))
    )
    (net (code "17") (name "MAG_VENTIL1") (class "Default")
      (node (ref "MAGVENT1") (pin "1") (pinfunction "1_1") (pintype "passive"))
      (node (ref "U$1") (pin "1") (pinfunction "OUT_1") (pintype "output"))
    )
    (net (code "18") (name "MAG_VENTIL2") (class "Default")
      (node (ref "MAGVENT2") (pin "1") (pinfunction "1_1") (pintype "passive"))
      (node (ref "U$4") (pin "1") (pinfunction "OUT_1") (pintype "output"))
    )
    (net (code "19") (name "Net-(GPIO_IN1-P)") (class "Default")
      (node (ref "GPIO_IN1") (pin "3") (pinfunction "P_3") (pintype "passive"))
      (node (ref "GPIO_IN1") (pin "4") (pinfunction "P1_4") (pintype "passive"))
      (node (ref "R1") (pin "2") (pinfunction "2_2") (pintype "passive"))
      (node (ref "R2") (pin "2") (pinfunction "2_2") (pintype "passive"))
    )
    (net (code "20") (name "Net-(GPIO_IN2-P)") (class "Default")
      (node (ref "GPIO_IN2") (pin "3") (pinfunction "P_3") (pintype "passive"))
      (node (ref "GPIO_IN2") (pin "4") (pinfunction "P1_4") (pintype "passive"))
      (node (ref "R3") (pin "2") (pinfunction "2_2") (pintype "passive"))
      (node (ref "R4") (pin "2") (pinfunction "2_2") (pintype "passive"))
    )
    (net (code "21") (name "Net-(GPIO_IN3-P)") (class "Default")
      (node (ref "GPIO_IN3") (pin "3") (pinfunction "P_3") (pintype "passive"))
      (node (ref "GPIO_IN3") (pin "4") (pinfunction "P1_4") (pintype "passive"))
      (node (ref "R5") (pin "2") (pinfunction "2_2") (pintype "passive"))
      (node (ref "R6") (pin "2") (pinfunction "2_2") (pintype "passive"))
    )
    (net (code "22") (name "Net-(IC1A-NRST)") (class "Default")
      (node (ref "C18") (pin "2") (pinfunction "2_2") (pintype "passive"))
      (node (ref "IC1") (pin "7") (pinfunction "NRST_7") (pintype "bidirectional"))
      (node (ref "S1") (pin "3") (pinfunction "P_3") (pintype "passive"))
      (node (ref "S1") (pin "4") (pinfunction "P1_4") (pintype "passive"))
    )
    (net (code "23") (name "Net-(IC1A-OSC_IN{slash}PH0)") (class "Default")
      (node (ref "C16") (pin "1") (pinfunction "1_1") (pintype "passive"))
      (node (ref "IC1") (pin "5") (pinfunction "OSC_IN/PH0_5") (pintype "bidirectional"))
      (node (ref "Q1") (pin "2") (pinfunction "2_2") (pintype "passive"))
    )
    (net (code "24") (name "Net-(IC1A-OSC_OUT{slash}PH1)") (class "Default")
      (node (ref "C17") (pin "1") (pinfunction "1_1") (pintype "passive"))
      (node (ref "IC1") (pin "6") (pinfunction "OSC_OUT/PH1_6") (pintype "bidirectional"))
      (node (ref "Q1") (pin "1") (pinfunction "1_1") (pintype "passive"))
    )
    (net (code "25") (name "Net-(IC1A-VCAP_1)") (class "Default")
      (node (ref "C14") (pin "1") (pinfunction "1_1") (pintype "passive"))
      (node (ref "IC1") (pin "31") (pinfunction "VCAP_1_31") (pintype "bidirectional"))
    )
    (net (code "26") (name "Net-(IC1A-VCAP_2)") (class "Default")
      (node (ref "C11") (pin "1") (pinfunction "1_1") (pintype "passive"))
      (node (ref "IC1") (pin "47") (pinfunction "VCAP_2_47") (pintype "bidirectional"))
    )
    (net (code "27") (name "Net-(Q2-B)") (class "Default")
      (node (ref "Q2") (pin "1") (pinfunction "B_1") (pintype "passive"))
      (node (ref "U12") (pin "6") (pinfunction "B_6") (pintype "input"))
    )
    (net (code "28") (name "Net-(Q2-E)") (class "Default")
      (node (ref "Q2") (pin "3") (pinfunction "E_3") (pintype "passive"))
      (node (ref "U12") (pin "5") (pinfunction "E_5") (pintype "input"))
    )
    (net (code "29") (name "Net-(U$2-VINA-)") (class "Default")
      (node (ref "R13") (pin "1") (pinfunction "1_1") (pintype "passive"))
      (node (ref "U$2") (pin "1") (pinfunction "VOUTA_1") (pintype "output"))
      (node (ref "U$2") (pin "2") (pinfunction "VINA-_2") (pintype "input"))
    )
    (net (code "30") (name "Net-(U$2-VINB-)") (class "Default")
      (node (ref "R14") (pin "1") (pinfunction "1_1") (pintype "passive"))
      (node (ref "U$2") (pin "6") (pinfunction "VINB-_6") (pintype "input"))
      (node (ref "U$2") (pin "7") (pinfunction "VOUTB_7") (pintype "output"))
    )
    (net (code "31") (name "Net-(U11-COMPTR_NEG)") (class "Default")
      (node (ref "R64") (pin "2") (pinfunction "2_2") (pintype "passive"))
      (node (ref "R65") (pin "1") (pinfunction "1_1") (pintype "passive"))
      (node (ref "U11") (pin "5") (pinfunction "COMPTR_NEG_5") (pintype "input"))
    )
    (net (code "32") (name "Net-(U11-CT)") (class "Default")
      (node (ref "C60") (pin "1") (pinfunction "1_1") (pintype "passive"))
      (node (ref "U11") (pin "3") (pinfunction "CT_3") (pintype "output"))
    )
    (net (code "33") (name "Net-(U11-DRVR_C)") (class "Default")
      (node (ref "R63") (pin "2") (pinfunction "2_2") (pintype "passive"))
      (node (ref "U11") (pin "8") (pinfunction "DRVR_C_8") (pintype "input"))
    )
    (net (code "34") (name "Net-(U11-IPK_SENSE)") (class "Default")
      (node (ref "L2") (pin "1") (pinfunction "1_1") (pintype "passive"))
      (node (ref "R62") (pin "2") (pinfunction "2_2") (pintype "passive"))
      (node (ref "R63") (pin "1") (pinfunction "1_1") (pintype "passive"))
      (node (ref "U11") (pin "7") (pinfunction "IPK_SENSE_7") (pintype "passive"))
    )
    (net (code "35") (name "Net-(U11-SW_C)") (class "Default")
      (node (ref "D15") (pin "A") (pinfunction "A_A") (pintype "passive"))
      (node (ref "L2") (pin "2") (pinfunction "2_2") (pintype "passive"))
      (node (ref "U11") (pin "1") (pinfunction "SW_C_1") (pintype "output"))
    )
    (net (code "36") (name "Net-(U12-IIN)") (class "Default")
      (node (ref "R66") (pin "2") (pinfunction "2_2") (pintype "passive"))
      (node (ref "U12") (pin "2") (pinfunction "IIN_2") (pintype "input"))
    )
    (net (code "37") (name "Net-(U12-IRET)") (class "Default")
      (node (ref "R67") (pin "1") (pinfunction "1_1") (pintype "passive"))
      (node (ref "R68") (pin "1") (pinfunction "1_1") (pintype "passive"))
      (node (ref "U12") (pin "3") (pinfunction "IRET_3") (pintype "input"))
    )
    (net (code "38") (name "Net-(U12-VREF)") (class "Default")
      (node (ref "R67") (pin "2") (pinfunction "2_2") (pintype "passive"))
      (node (ref "U12") (pin "1") (pinfunction "VREF_1") (pintype "passive"))
    )
    (net (code "39") (name "Net-(U12-VREG)") (class "Default")
      (node (ref "R68") (pin "2") (pinfunction "2_2") (pintype "passive"))
      (node (ref "U12") (pin "8") (pinfunction "VREG_8") (pintype "passive"))
    )
    (net (code "40") (name "SENSOR1_IN") (class "Default")
      (node (ref "D3") (pin "3") (pinfunction "AC_3") (pintype "passive"))
      (node (ref "R9") (pin "2") (pinfunction "2_2") (pintype "passive"))
      (node (ref "SENS1") (pin "1") (pinfunction "1_1") (pintype "passive"))
      (node (ref "U$2") (pin "3") (pinfunction "VINA+_3") (pintype "input"))
    )
    (net (code "41") (name "SENSOR1_OUT") (class "Default")
      (node (ref "C26") (pin "1") (pinfunction "1_1") (pintype "passive"))
      (node (ref "IC1") (pin "17") (pinfunction "PA3_17") (pintype "bidirectional"))
      (node (ref "R13") (pin "2") (pinfunction "2_2") (pintype "passive"))
      (node (ref "R16") (pin "2") (pinfunction "2_2") (pintype "passive"))
      (node (ref "SEN1") (pin "TP") (pinfunction "TP_TP") (pintype "input"))
    )
    (net (code "42") (name "SENSOR2_IN") (class "Default")
      (node (ref "D4") (pin "3") (pinfunction "AC_3") (pintype "passive"))
      (node (ref "R12") (pin "2") (pinfunction "2_2") (pintype "passive"))
      (node (ref "SENS2") (pin "1") (pinfunction "1_1") (pintype "passive"))
      (node (ref "U$2") (pin "5") (pinfunction "VINB+_5") (pintype "input"))
    )
    (net (code "43") (name "SENSOR2_OUT") (class "Default")
      (node (ref "C25") (pin "1") (pinfunction "1_1") (pintype "passive"))
      (node (ref "IC1") (pin "21") (pinfunction "PA5_21") (pintype "bidirectional"))
      (node (ref "R14") (pin "2") (pinfunction "2_2") (pintype "passive"))
      (node (ref "R15") (pin "1") (pinfunction "1_1") (pintype "passive"))
      (node (ref "SEN2") (pin "TP") (pinfunction "TP_TP") (pintype "input"))
    )
    (net (code "44") (name "SYS_NRST") (class "Default")
      (node (ref "SWDIO_DEBUGGER") (pin "5") (pinfunction "5_5") (pintype "passive"))
    )
    (net (code "45") (name "SYS_SWCLK") (class "Default")
      (node (ref "IC1") (pin "49") (pinfunction "PA14_49") (pintype "bidirectional"))
      (node (ref "SWDIO_DEBUGGER") (pin "2") (pinfunction "2_2") (pintype "passive"))
    )
    (net (code "46") (name "SYS_SWDIO") (class "Default")
      (node (ref "IC1") (pin "46") (pinfunction "PA13_46") (pintype "bidirectional"))
      (node (ref "SWDIO_DEBUGGER") (pin "4") (pinfunction "4_4") (pintype "passive"))
    )
    (net (code "47") (name "V_IN") (class "Default")
      (node (ref "D1") (pin "C") (pinfunction "C_C") (pintype "passive"))
      (node (ref "L1") (pin "1") (pinfunction "1_1") (pintype "passive"))
      (node (ref "PWSPLY") (pin "1") (pinfunction "1_1") (pintype "passive"))
    )
    (net (code "48") (name "unconnected-(IC1B-PA0-Pad14)") (class "Default")
      (node (ref "IC1") (pin "14") (pinfunction "PA0_14") (pintype "bidirectional"))
    )
    (net (code "49") (name "unconnected-(IC1B-PA8-Pad41)") (class "Default")
      (node (ref "IC1") (pin "41") (pinfunction "PA8_41") (pintype "bidirectional"))
    )
    (net (code "50") (name "unconnected-(IC1B-PA9-Pad42)") (class "Default")
      (node (ref "IC1") (pin "42") (pinfunction "PA9_42") (pintype "bidirectional"))
    )
    (net (code "51") (name "unconnected-(IC1B-PA10-Pad43)") (class "Default")
      (node (ref "IC1") (pin "43") (pinfunction "PA10_43") (pintype "bidirectional"))
    )
    (net (code "52") (name "unconnected-(IC1B-PA11-Pad44)") (class "Default")
      (node (ref "IC1") (pin "44") (pinfunction "PA11_44") (pintype "bidirectional"))
    )
    (net (code "53") (name "unconnected-(IC1B-PA12-Pad45)") (class "Default")
      (node (ref "IC1") (pin "45") (pinfunction "PA12_45") (pintype "bidirectional"))
    )
    (net (code "54") (name "unconnected-(IC1B-PA15-Pad50)") (class "Default")
      (node (ref "IC1") (pin "50") (pinfunction "PA15_50") (pintype "bidirectional"))
    )
    (net (code "55") (name "unconnected-(IC1B-PB3-Pad55)") (class "Default")
      (node (ref "IC1") (pin "55") (pinfunction "PB3_55") (pintype "bidirectional"))
    )
    (net (code "56") (name "unconnected-(IC1B-PB4-Pad56)") (class "Default")
      (node (ref "IC1") (pin "56") (pinfunction "PB4_56") (pintype "bidirectional"))
    )
    (net (code "57") (name "unconnected-(IC1B-PB5-Pad57)") (class "Default")
      (node (ref "IC1") (pin "57") (pinfunction "PB5_57") (pintype "bidirectional"))
    )
    (net (code "58") (name "unconnected-(IC1B-PB6-Pad58)") (class "Default")
      (node (ref "IC1") (pin "58") (pinfunction "PB6_58") (pintype "bidirectional"))
    )
    (net (code "59") (name "unconnected-(IC1B-PB7-Pad59)") (class "Default")
      (node (ref "IC1") (pin "59") (pinfunction "PB7_59") (pintype "bidirectional"))
    )
    (net (code "60") (name "unconnected-(IC1B-PB8-Pad61)") (class "Default")
      (node (ref "IC1") (pin "61") (pinfunction "PB8_61") (pintype "bidirectional"))
    )
    (net (code "61") (name "unconnected-(IC1B-PB9-Pad62)") (class "Default")
      (node (ref "IC1") (pin "62") (pinfunction "PB9_62") (pintype "bidirectional"))
    )
    (net (code "62") (name "unconnected-(IC1B-PB10-Pad29)") (class "Default")
      (node (ref "IC1") (pin "29") (pinfunction "PB10_29") (pintype "bidirectional"))
    )
    (net (code "63") (name "unconnected-(IC1B-PB11-Pad30)") (class "Default")
      (node (ref "IC1") (pin "30") (pinfunction "PB11_30") (pintype "bidirectional"))
    )
    (net (code "64") (name "unconnected-(IC1B-PB12-Pad33)") (class "Default")
      (node (ref "IC1") (pin "33") (pinfunction "PB12_33") (pintype "bidirectional"))
    )
    (net (code "65") (name "unconnected-(IC1B-PB13-Pad34)") (class "Default")
      (node (ref "IC1") (pin "34") (pinfunction "PB13_34") (pintype "bidirectional"))
    )
    (net (code "66") (name "unconnected-(IC1B-PB14-Pad35)") (class "Default")
      (node (ref "IC1") (pin "35") (pinfunction "PB14_35") (pintype "bidirectional"))
    )
    (net (code "67") (name "unconnected-(IC1B-PB15-Pad36)") (class "Default")
      (node (ref "IC1") (pin "36") (pinfunction "PB15_36") (pintype "bidirectional"))
    )
    (net (code "68") (name "unconnected-(IC1B-PC0-Pad8)") (class "Default")
      (node (ref "IC1") (pin "8") (pinfunction "PC0_8") (pintype "bidirectional"))
    )
    (net (code "69") (name "unconnected-(IC1B-PC1-Pad9)") (class "Default")
      (node (ref "IC1") (pin "9") (pinfunction "PC1_9") (pintype "bidirectional"))
    )
    (net (code "70") (name "unconnected-(IC1B-PC2-Pad10)") (class "Default")
      (node (ref "IC1") (pin "10") (pinfunction "PC2_10") (pintype "bidirectional"))
    )
    (net (code "71") (name "unconnected-(IC1B-PC3-Pad11)") (class "Default")
      (node (ref "IC1") (pin "11") (pinfunction "PC3_11") (pintype "bidirectional"))
    )
    (net (code "72") (name "unconnected-(IC1B-PC4-Pad24)") (class "Default")
      (node (ref "IC1") (pin "24") (pinfunction "PC4_24") (pintype "bidirectional"))
    )
    (net (code "73") (name "unconnected-(IC1B-PC5-Pad25)") (class "Default")
      (node (ref "IC1") (pin "25") (pinfunction "PC5_25") (pintype "bidirectional"))
    )
    (net (code "74") (name "unconnected-(IC1B-PC6-Pad37)") (class "Default")
      (node (ref "IC1") (pin "37") (pinfunction "PC6_37") (pintype "bidirectional"))
    )
    (net (code "75") (name "unconnected-(IC1B-PC7-Pad38)") (class "Default")
      (node (ref "IC1") (pin "38") (pinfunction "PC7_38") (pintype "bidirectional"))
    )
    (net (code "76") (name "unconnected-(IC1B-PC10-Pad51)") (class "Default")
      (node (ref "IC1") (pin "51") (pinfunction "PC10_51") (pintype "bidirectional"))
    )
    (net (code "77") (name "unconnected-(IC1B-PC11-Pad52)") (class "Default")
      (node (ref "IC1") (pin "52") (pinfunction "PC11_52") (pintype "bidirectional"))
    )
    (net (code "78") (name "unconnected-(IC1B-PC12-Pad53)") (class "Default")
      (node (ref "IC1") (pin "53") (pinfunction "PC12_53") (pintype "bidirectional"))
    )
    (net (code "79") (name "unconnected-(IC1B-PC13-Pad2)") (class "Default")
      (node (ref "IC1") (pin "2") (pinfunction "PC13_2") (pintype "bidirectional"))
    )
    (net (code "80") (name "unconnected-(IC1B-PC14-Pad3)") (class "Default")
      (node (ref "IC1") (pin "3") (pinfunction "PC14_3") (pintype "bidirectional"))
    )
    (net (code "81") (name "unconnected-(IC1B-PC15-Pad4)") (class "Default")
      (node (ref "IC1") (pin "4") (pinfunction "PC15_4") (pintype "bidirectional"))
    )
    (net (code "82") (name "unconnected-(IC1B-PD2-Pad54)") (class "Default")
      (node (ref "IC1") (pin "54") (pinfunction "PD2_54") (pintype "bidirectional"))
    )
  )
)
